# EasyEDA_Source_v2_e.net
KiCad netlist of a schematic drawn in EasyEDA
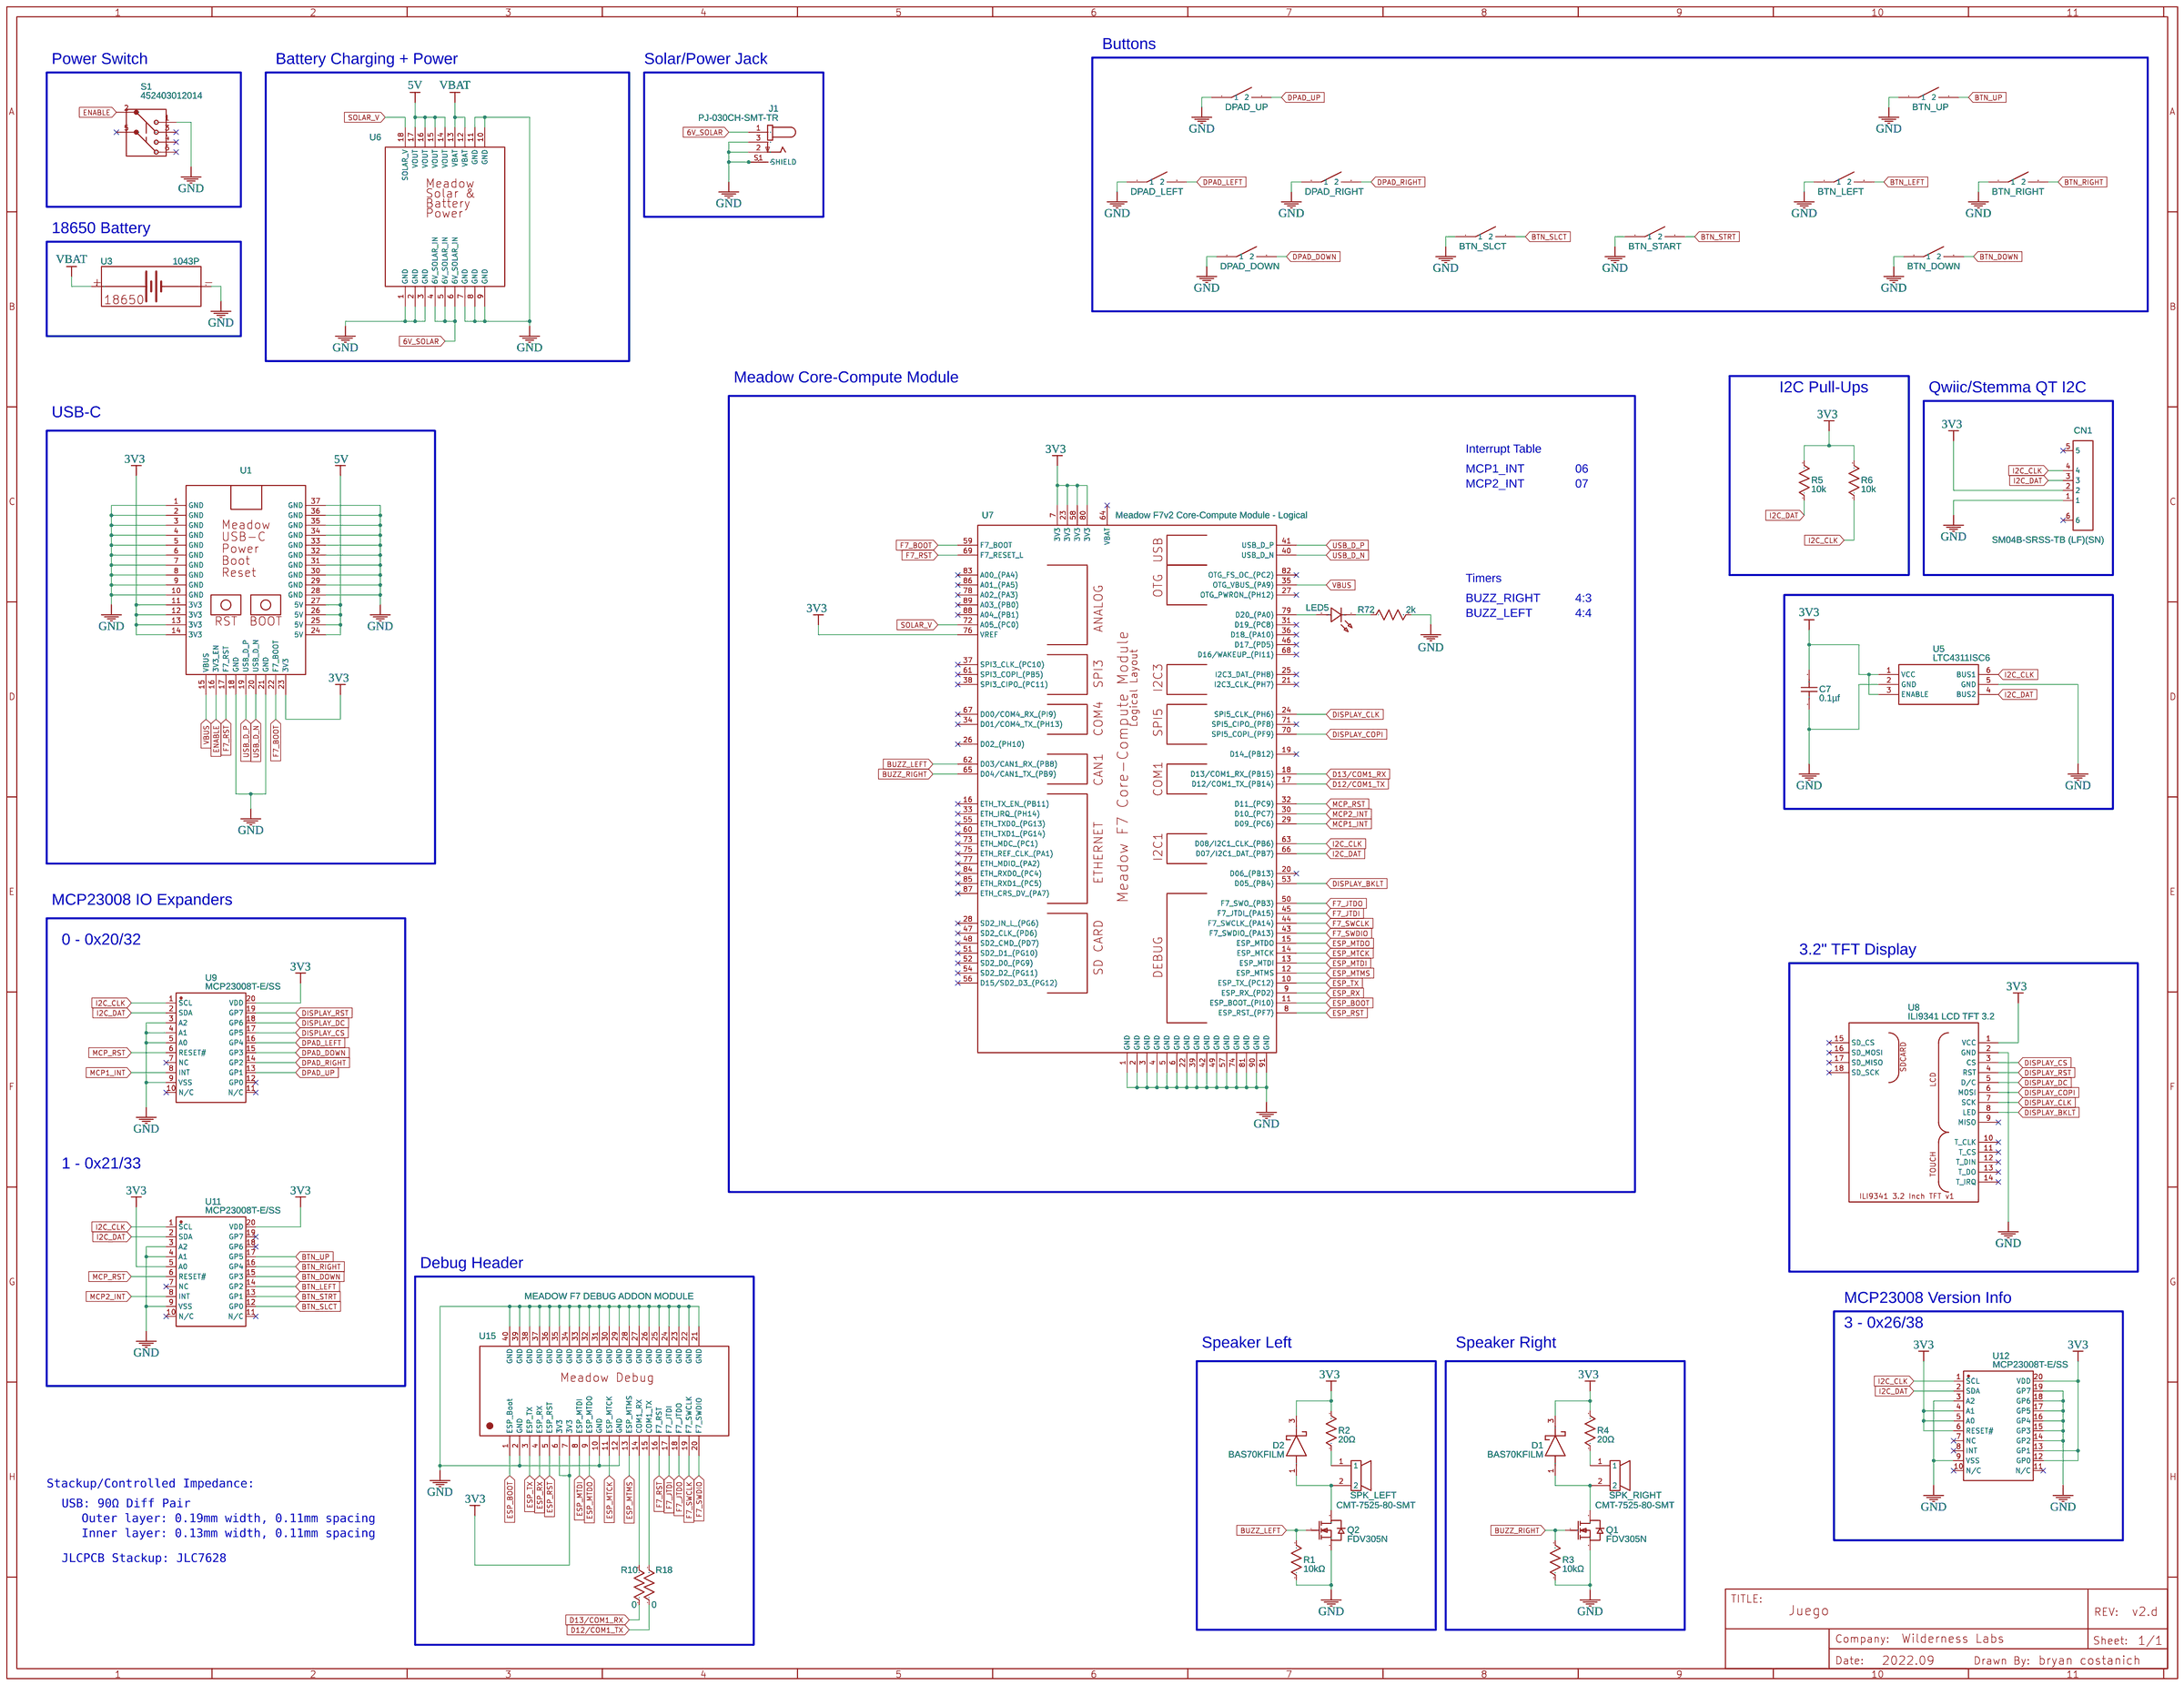
[diagram p0: schematic sheet]

(export (version "E")
  (design (tool "Eeschema 10.0.6"))
  (components
    (comp (ref "BTN_DOWN") (value "Up") (libsource (lib "") (part "Tactile Switch 6x6 SMD_5")))
    (comp (ref "BTN_LEFT") (value "Up") (libsource (lib "") (part "Tactile Switch 6x6 SMD_1")))
    (comp (ref "BTN_RIGHT") (value "Up") (libsource (lib "") (part "Tactile Switch 6x6 SMD_2")))
    (comp (ref "BTN_SLCT") (value "Up") (libsource (lib "") (part "Tactile Switch 6x6 SMD_6")))
    (comp (ref "BTN_START") (value "Up") (libsource (lib "") (part "Tactile Switch 6x6 SMD_8")))
    (comp (ref "BTN_UP") (value "Up") (libsource (lib "") (part "Tactile Switch 6x6 SMD_3")))
    (comp (ref "C7")
      (value "0.1µf")
      (fields
        (field (name "BOM_Manufacturer Part") "CC0603KRX7R7BB104")
        (field (name "BOM_Supplier Part") "C108079")
      )
      (libsource (lib "") (part "CC0603KRX7R7BB104"))
    )
    (comp (ref "CN1")
      (value "SM04B-SRSS-TB (LF)(SN)")
      (fields (field (name "BOM_Supplier Part") "C160404"))
      (libsource (lib "") (part "SM04B-SRSS-TB (LF)(SN)"))
    )
    (comp (ref "D1") (value "BAS70KFILM") (libsource (lib "") (part "BAS70KFILM")))
    (comp (ref "D2") (value "BAS70KFILM") (libsource (lib "") (part "BAS70KFILM")))
    (comp (ref "DPAD_DOWN") (value "Up") (libsource (lib "") (part "Tactile Switch 6x6 SMD")))
    (comp (ref "DPAD_LEFT") (value "Up") (libsource (lib "") (part "Tactile Switch 6x6 SMD_9")))
    (comp (ref "DPAD_RIGHT") (value "Up") (libsource (lib "") (part "Tactile Switch 6x6 SMD_7")))
    (comp (ref "DPAD_UP") (value "Up") (libsource (lib "") (part "Tactile Switch 6x6 SMD_4")))
    (comp (ref "J1") (value "PJ-030CH-SMT-TR") (libsource (lib "") (part "PJ-030CH-SMT-TR")))
    (comp (ref "LED5") (value "EAST1608GA0") (libsource (lib "") (part "EAST1608GA0")))
    (comp (ref "Q1")
      (value "FDV305N")
      (fields (field (name "BOM_Supplier Part") "C65189"))
      (libsource (lib "") (part "2N7002"))
    )
    (comp (ref "Q2")
      (value "FDV305N")
      (fields (field (name "BOM_Supplier Part") "C65189"))
      (libsource (lib "") (part "2N7002"))
    )
    (comp (ref "R1")
      (value "10kΩ")
      (fields (field (name "BOM_Manufacturer Part") "RC0603FR-0710KL"))
      (libsource (lib "") (part "R_0402_US"))
    )
    (comp (ref "R2")
      (value "20Ω")
      (fields (field (name "BOM_Manufacturer Part") "RC0603FR-0720RL"))
      (libsource (lib "") (part "R_0402_US"))
    )
    (comp (ref "R3")
      (value "10kΩ")
      (fields (field (name "BOM_Manufacturer Part") "RC0603FR-0710KL"))
      (libsource (lib "") (part "R_0402_US"))
    )
    (comp (ref "R4")
      (value "20Ω")
      (fields (field (name "BOM_Manufacturer Part") "RC0603FR-0720RL"))
      (libsource (lib "") (part "R_0402_US"))
    )
    (comp (ref "R5")
      (value "10k")
      (fields (field (name "BOM_Manufacturer Part") "RC0603FR-0710KL"))
      (libsource (lib "") (part "Res_0603(1/10W)_US"))
    )
    (comp (ref "R6")
      (value "10k")
      (fields (field (name "BOM_Manufacturer Part") "RC0603FR-0710KL"))
      (libsource (lib "") (part "Res_0603(1/10W)_US"))
    )
    (comp (ref "R10")
      (value "0")
      (fields (field (name "BOM_Manufacturer Part") "RC0603JR-070RL"))
      (libsource (lib "") (part "R_0603_US"))
    )
    (comp (ref "R18")
      (value "0")
      (fields (field (name "BOM_Manufacturer Part") "RC0603JR-070RL"))
      (libsource (lib "") (part "R_0603_US"))
    )
    (comp (ref "R72")
      (value "2k")
      (fields (field (name "BOM_Manufacturer Part") "RC0603FR-072KL"))
      (libsource (lib "") (part "R_0603_US_1"))
    )
    (comp (ref "S1") (value "452403012014") (libsource (lib "") (part "452403012014")))
    (comp (ref "SPK_LEFT")
      (value "CMT-7525-80-SMT")
      (fields (field (name "BOM_Manufacturer Part") "CMT-7525-80-SMT-TR"))
      (libsource (lib "") (part "CMT-7525-80-SMT"))
    )
    (comp (ref "SPK_RIGHT")
      (value "CMT-7525-80-SMT")
      (fields (field (name "BOM_Manufacturer Part") "CMT-7525-80-SMT-TR"))
      (libsource (lib "") (part "CMT-7525-80-SMT_1"))
    )
    (comp (ref "U1")
      (value "Meadow Core-Compute USB-C, Power, Boot, and Reset Addon Module")
      (libsource (lib "") (part "Meadow Core-Compute USB-C, Power, Boot, and Reset Addon Module"))
    )
    (comp (ref "U3") (value "1043P") (libsource (lib "") (part "1043P")))
    (comp (ref "U5")
      (value "LTC4311ISC6")
      (fields (field (name "BOM_Manufacturer Part") "LTC4311ISC6#TRPBF"))
      (libsource (lib "") (part "LTC4311ISC6"))
    )
    (comp (ref "U6")
      (value "Meadow Core-Compute Addon Module - Solar Battery Power")
      (libsource (lib "") (part "Meadow Core-Compute Addon Module - Solar Battery Power"))
    )
    (comp (ref "U7")
      (value "Meadow F7v2 Core-Compute Module - Logical")
      (libsource (lib "") (part "Meadow F7v2 Core-Compute Module - Logical"))
    )
    (comp (ref "U8") (value "ILI9341 LCD TFT 3.2") (libsource (lib "") (part "ILI9341 LCD TFT 3.2")))
    (comp (ref "U9")
      (value "MCP23008T-E/SS")
      (fields (field (name "BOM_Supplier Part") "C629435"))
      (libsource (lib "") (part "MCP23008T-E/SS"))
    )
    (comp (ref "U11")
      (value "MCP23008T-E/SS")
      (fields (field (name "BOM_Supplier Part") "C629435"))
      (libsource (lib "") (part "MCP23008T-E/SS"))
    )
    (comp (ref "U12")
      (value "MCP23008T-E/SS")
      (fields (field (name "BOM_Supplier Part") "C629435"))
      (libsource (lib "") (part "MCP23008T-E/SS"))
    )
    (comp (ref "U15")
      (value "MEADOW F7 DEBUG ADDON MODULE")
      (libsource (lib "") (part "MEADOW F7 DEBUG ADDON MODULE"))
    )
  )
  (nets
    (net (code "1") (name "3V3") (class "Default")
      (node (ref "C7") (pin "2") (pinfunction "2_2") (pintype "unspecified"))
      (node (ref "CN1") (pin "2") (pinfunction "2_2") (pintype "unspecified"))
      (node (ref "D1") (pin "3") (pinfunction "K_3") (pintype "bidirectional"))
      (node (ref "D2") (pin "3") (pinfunction "K_3") (pintype "bidirectional"))
      (node (ref "R2") (pin "2") (pinfunction "2_2") (pintype "unspecified"))
      (node (ref "R4") (pin "2") (pinfunction "2_2") (pintype "unspecified"))
      (node (ref "R5") (pin "2") (pinfunction "2_2") (pintype "unspecified"))
      (node (ref "R6") (pin "2") (pinfunction "2_2") (pintype "unspecified"))
      (node (ref "U1") (pin "11") (pinfunction "3V3_11") (pintype "unspecified"))
      (node (ref "U1") (pin "12") (pinfunction "3V3_12") (pintype "unspecified"))
      (node (ref "U1") (pin "13") (pinfunction "3V3_13") (pintype "unspecified"))
      (node (ref "U1") (pin "14") (pinfunction "3V3_14") (pintype "unspecified"))
      (node (ref "U1") (pin "23") (pinfunction "3V3_23") (pintype "passive"))
      (node (ref "U11") (pin "20") (pinfunction "VDD_20") (pintype "unspecified"))
      (node (ref "U11") (pin "5") (pinfunction "A0_5") (pintype "unspecified"))
      (node (ref "U12") (pin "12") (pinfunction "GP0_12") (pintype "unspecified"))
      (node (ref "U12") (pin "13") (pinfunction "GP1_13") (pintype "unspecified"))
      (node (ref "U12") (pin "20") (pinfunction "VDD_20") (pintype "unspecified"))
      (node (ref "U12") (pin "4") (pinfunction "A1_4") (pintype "unspecified"))
      (node (ref "U12") (pin "5") (pinfunction "A0_5") (pintype "unspecified"))
      (node (ref "U12") (pin "6") (pinfunction "RESET#_6") (pintype "unspecified"))
      (node (ref "U15") (pin "6") (pinfunction "3V3_6") (pintype "unspecified"))
      (node (ref "U15") (pin "7") (pinfunction "3V3_7") (pintype "unspecified"))
      (node (ref "U5") (pin "1") (pinfunction "VCC_1") (pintype "unspecified"))
      (node (ref "U5") (pin "3") (pinfunction "ENABLE_3") (pintype "unspecified"))
      (node (ref "U7") (pin "23") (pinfunction "3V3_23") (pintype "unspecified"))
      (node (ref "U7") (pin "58") (pinfunction "3V3_58") (pintype "passive"))
      (node (ref "U7") (pin "7") (pinfunction "3V3_7") (pintype "unspecified"))
      (node (ref "U7") (pin "76") (pinfunction "VREF_76") (pintype "input"))
      (node (ref "U7") (pin "80") (pinfunction "3V3_80") (pintype "unspecified"))
      (node (ref "U8") (pin "1") (pinfunction "VCC_1") (pintype "unspecified"))
      (node (ref "U9") (pin "20") (pinfunction "VDD_20") (pintype "unspecified"))
    )
    (net (code "2") (name "5V") (class "Default")
      (node (ref "U1") (pin "24") (pinfunction "5V_24") (pintype "passive"))
      (node (ref "U1") (pin "25") (pinfunction "5V_25") (pintype "passive"))
      (node (ref "U1") (pin "26") (pinfunction "5V_26") (pintype "passive"))
      (node (ref "U1") (pin "27") (pinfunction "5V_27") (pintype "passive"))
      (node (ref "U6") (pin "14") (pinfunction "VOUT_14") (pintype "unspecified"))
      (node (ref "U6") (pin "15") (pinfunction "VOUT_15") (pintype "unspecified"))
      (node (ref "U6") (pin "16") (pinfunction "VOUT_16") (pintype "unspecified"))
      (node (ref "U6") (pin "17") (pinfunction "VOUT_17") (pintype "unspecified"))
    )
    (net (code "3") (name "6V_SOLAR") (class "Default")
      (node (ref "J1") (pin "1") (pinfunction "1_1") (pintype "bidirectional"))
      (node (ref "U6") (pin "4") (pinfunction "6V_SOLAR_IN_4") (pintype "unspecified"))
      (node (ref "U6") (pin "5") (pinfunction "6V_SOLAR_IN_5") (pintype "unspecified"))
      (node (ref "U6") (pin "6") (pinfunction "6V_SOLAR_IN_6") (pintype "unspecified"))
    )
    (net (code "4") (name "BTN_DOWN") (class "Default")
      (node (ref "BTN_DOWN") (pin "B1") (pinfunction "2_B1") (pintype "unspecified"))
      (node (ref "U11") (pin "15") (pinfunction "GP3_15") (pintype "unspecified"))
    )
    (net (code "5") (name "BTN_LEFT") (class "Default")
      (node (ref "BTN_LEFT") (pin "B1") (pinfunction "2_B1") (pintype "unspecified"))
      (node (ref "U11") (pin "14") (pinfunction "GP2_14") (pintype "unspecified"))
    )
    (net (code "6") (name "BTN_RIGHT") (class "Default")
      (node (ref "BTN_RIGHT") (pin "B1") (pinfunction "2_B1") (pintype "unspecified"))
      (node (ref "U11") (pin "16") (pinfunction "GP4_16") (pintype "unspecified"))
    )
    (net (code "7") (name "BTN_SLCT") (class "Default")
      (node (ref "BTN_SLCT") (pin "B1") (pinfunction "2_B1") (pintype "unspecified"))
      (node (ref "U11") (pin "12") (pinfunction "GP0_12") (pintype "unspecified"))
    )
    (net (code "8") (name "BTN_STRT") (class "Default")
      (node (ref "BTN_START") (pin "B1") (pinfunction "2_B1") (pintype "unspecified"))
      (node (ref "U11") (pin "13") (pinfunction "GP1_13") (pintype "unspecified"))
    )
    (net (code "9") (name "BTN_UP") (class "Default")
      (node (ref "BTN_UP") (pin "B1") (pinfunction "2_B1") (pintype "unspecified"))
      (node (ref "U11") (pin "17") (pinfunction "GP5_17") (pintype "unspecified"))
    )
    (net (code "10") (name "BUZZ_LEFT") (class "Default")
      (node (ref "Q2") (pin "1") (pinfunction "G_1") (pintype "unspecified"))
      (node (ref "R1") (pin "2") (pinfunction "2_2") (pintype "unspecified"))
      (node (ref "U7") (pin "62") (pinfunction "D03/CAN1_RX_(PB8)_62") (pintype "unspecified"))
    )
    (net (code "11") (name "BUZZ_RIGHT") (class "Default")
      (node (ref "Q1") (pin "1") (pinfunction "G_1") (pintype "unspecified"))
      (node (ref "R3") (pin "2") (pinfunction "2_2") (pintype "unspecified"))
      (node (ref "U7") (pin "65") (pinfunction "D04/CAN1_TX_(PB9)_65") (pintype "unspecified"))
    )
    (net (code "12") (name "D12{slash}COM1_TX") (class "Default")
      (node (ref "R18") (pin "1") (pinfunction "1_1") (pintype "unspecified"))
      (node (ref "U7") (pin "17") (pinfunction "D12/COM1_TX_(PB14)_17") (pintype "unspecified"))
    )
    (net (code "13") (name "D13{slash}COM1_RX") (class "Default")
      (node (ref "R10") (pin "1") (pinfunction "1_1") (pintype "unspecified"))
      (node (ref "U7") (pin "18") (pinfunction "D13/COM1_RX_(PB15)_18") (pintype "unspecified"))
    )
    (net (code "14") (name "DISPLAY_BKLT") (class "Default")
      (node (ref "U7") (pin "53") (pinfunction "D05_(PB4)_53") (pintype "unspecified"))
      (node (ref "U8") (pin "8") (pinfunction "LED_8") (pintype "unspecified"))
    )
    (net (code "15") (name "DISPLAY_CLK") (class "Default")
      (node (ref "U7") (pin "24") (pinfunction "SPI5_CLK_(PH6)_24") (pintype "unspecified"))
      (node (ref "U8") (pin "7") (pinfunction "SCK_7") (pintype "unspecified"))
    )
    (net (code "16") (name "DISPLAY_COPI") (class "Default")
      (node (ref "U7") (pin "70") (pinfunction "SPI5_COPI_(PF9)_70") (pintype "unspecified"))
      (node (ref "U8") (pin "6") (pinfunction "MOSI_6") (pintype "unspecified"))
    )
    (net (code "17") (name "DISPLAY_CS") (class "Default")
      (node (ref "U8") (pin "3") (pinfunction "CS_3") (pintype "unspecified"))
      (node (ref "U9") (pin "17") (pinfunction "GP5_17") (pintype "unspecified"))
    )
    (net (code "18") (name "DISPLAY_DC") (class "Default")
      (node (ref "U8") (pin "5") (pinfunction "D/C_5") (pintype "unspecified"))
      (node (ref "U9") (pin "18") (pinfunction "GP6_18") (pintype "unspecified"))
    )
    (net (code "19") (name "DISPLAY_RST") (class "Default")
      (node (ref "U8") (pin "4") (pinfunction "RST_4") (pintype "unspecified"))
      (node (ref "U9") (pin "19") (pinfunction "GP7_19") (pintype "unspecified"))
    )
    (net (code "20") (name "DPAD_DOWN") (class "Default")
      (node (ref "DPAD_DOWN") (pin "B1") (pinfunction "2_B1") (pintype "unspecified"))
      (node (ref "U9") (pin "15") (pinfunction "GP3_15") (pintype "unspecified"))
    )
    (net (code "21") (name "DPAD_LEFT") (class "Default")
      (node (ref "DPAD_LEFT") (pin "B1") (pinfunction "2_B1") (pintype "unspecified"))
      (node (ref "U9") (pin "16") (pinfunction "GP4_16") (pintype "unspecified"))
    )
    (net (code "22") (name "DPAD_RIGHT") (class "Default")
      (node (ref "DPAD_RIGHT") (pin "B1") (pinfunction "2_B1") (pintype "unspecified"))
      (node (ref "U9") (pin "14") (pinfunction "GP2_14") (pintype "unspecified"))
    )
    (net (code "23") (name "DPAD_UP") (class "Default")
      (node (ref "DPAD_UP") (pin "B1") (pinfunction "2_B1") (pintype "unspecified"))
      (node (ref "U9") (pin "13") (pinfunction "GP1_13") (pintype "unspecified"))
    )
    (net (code "24") (name "ENABLE") (class "Default")
      (node (ref "S1") (pin "2") (pinfunction "1_2") (pintype "unspecified"))
      (node (ref "U1") (pin "16") (pinfunction "3V3_EN_16") (pintype "unspecified"))
    )
    (net (code "25") (name "ESP_BOOT") (class "Default")
      (node (ref "U15") (pin "1") (pinfunction "ESP_Boot_1") (pintype "unspecified"))
      (node (ref "U7") (pin "11") (pinfunction "ESP_BOOT_(PI10)_11") (pintype "unspecified"))
    )
    (net (code "26") (name "ESP_MTCK") (class "Default")
      (node (ref "U15") (pin "11") (pinfunction "ESP_MTCK_11") (pintype "unspecified"))
      (node (ref "U7") (pin "14") (pinfunction "ESP_MTCK_14") (pintype "unspecified"))
    )
    (net (code "27") (name "ESP_MTDI") (class "Default")
      (node (ref "U15") (pin "8") (pinfunction "ESP_MTDI_8") (pintype "unspecified"))
      (node (ref "U7") (pin "13") (pinfunction "ESP_MTDI_13") (pintype "unspecified"))
    )
    (net (code "28") (name "ESP_MTDO") (class "Default")
      (node (ref "U15") (pin "9") (pinfunction "ESP_MTDO_9") (pintype "unspecified"))
      (node (ref "U7") (pin "15") (pinfunction "ESP_MTDO_15") (pintype "unspecified"))
    )
    (net (code "29") (name "ESP_MTMS") (class "Default")
      (node (ref "U15") (pin "13") (pinfunction "ESP_MTMS_13") (pintype "unspecified"))
      (node (ref "U7") (pin "12") (pinfunction "ESP_MTMS_12") (pintype "unspecified"))
    )
    (net (code "30") (name "ESP_RST") (class "Default")
      (node (ref "U15") (pin "5") (pinfunction "ESP_RST_5") (pintype "unspecified"))
      (node (ref "U7") (pin "8") (pinfunction "ESP_RST_(PF7)_8") (pintype "unspecified"))
    )
    (net (code "31") (name "ESP_RX") (class "Default")
      (node (ref "U15") (pin "4") (pinfunction "ESP_RX_4") (pintype "unspecified"))
      (node (ref "U7") (pin "9") (pinfunction "ESP_RX_(PD2)_9") (pintype "unspecified"))
    )
    (net (code "32") (name "ESP_TX") (class "Default")
      (node (ref "U15") (pin "3") (pinfunction "ESP_TX_3") (pintype "unspecified"))
      (node (ref "U7") (pin "10") (pinfunction "ESP_TX_(PC12)_10") (pintype "unspecified"))
    )
    (net (code "33") (name "F7_BOOT") (class "Default")
      (node (ref "U1") (pin "22") (pinfunction "F7_BOOT_22") (pintype "unspecified"))
      (node (ref "U7") (pin "59") (pinfunction "F7_BOOT_59") (pintype "unspecified"))
    )
    (net (code "34") (name "F7_JTDI") (class "Default")
      (node (ref "U15") (pin "17") (pinfunction "F7_JTDI_17") (pintype "unspecified"))
      (node (ref "U7") (pin "45") (pinfunction "F7_JTDI_(PA15)_45") (pintype "unspecified"))
    )
    (net (code "35") (name "F7_JTDO") (class "Default")
      (node (ref "U15") (pin "18") (pinfunction "F7_JTDO_18") (pintype "unspecified"))
      (node (ref "U7") (pin "50") (pinfunction "F7_SWO_(PB3)_50") (pintype "unspecified"))
    )
    (net (code "36") (name "F7_RST") (class "Default")
      (node (ref "U1") (pin "17") (pinfunction "F7_RST_17") (pintype "unspecified"))
      (node (ref "U15") (pin "16") (pinfunction "F7_RST_16") (pintype "unspecified"))
      (node (ref "U7") (pin "69") (pinfunction "F7_RESET_L_69") (pintype "unspecified"))
    )
    (net (code "37") (name "F7_SWCLK") (class "Default")
      (node (ref "U15") (pin "19") (pinfunction "F7_SWCLK_19") (pintype "unspecified"))
      (node (ref "U7") (pin "44") (pinfunction "F7_SWCLK_(PA14)_44") (pintype "unspecified"))
    )
    (net (code "38") (name "F7_SWDIO") (class "Default")
      (node (ref "U15") (pin "20") (pinfunction "F7_SWDIO_20") (pintype "unspecified"))
      (node (ref "U7") (pin "43") (pinfunction "F7_SWDIO_(PA13)_43") (pintype "unspecified"))
    )
    (net (code "39") (name "GND") (class "Default")
      (node (ref "BTN_DOWN") (pin "A1") (pinfunction "1_A1") (pintype "unspecified"))
      (node (ref "BTN_LEFT") (pin "A1") (pinfunction "1_A1") (pintype "unspecified"))
      (node (ref "BTN_RIGHT") (pin "A1") (pinfunction "1_A1") (pintype "unspecified"))
      (node (ref "BTN_SLCT") (pin "A1") (pinfunction "1_A1") (pintype "unspecified"))
      (node (ref "BTN_START") (pin "A1") (pinfunction "1_A1") (pintype "unspecified"))
      (node (ref "BTN_UP") (pin "A1") (pinfunction "1_A1") (pintype "unspecified"))
      (node (ref "C7") (pin "1") (pinfunction "1_1") (pintype "unspecified"))
      (node (ref "CN1") (pin "1") (pinfunction "1_1") (pintype "unspecified"))
      (node (ref "DPAD_DOWN") (pin "A1") (pinfunction "1_A1") (pintype "unspecified"))
      (node (ref "DPAD_LEFT") (pin "A1") (pinfunction "1_A1") (pintype "unspecified"))
      (node (ref "DPAD_RIGHT") (pin "A1") (pinfunction "1_A1") (pintype "unspecified"))
      (node (ref "DPAD_UP") (pin "A1") (pinfunction "1_A1") (pintype "unspecified"))
      (node (ref "J1") (pin "2") (pinfunction "2_2") (pintype "bidirectional"))
      (node (ref "J1") (pin "3") (pinfunction "3_3") (pintype "bidirectional"))
      (node (ref "J1") (pin "S1") (pinfunction "SHIELD_S1") (pintype "bidirectional"))
      (node (ref "J1") (pin "S2") (pinfunction "SHIELD_S2") (pintype "bidirectional"))
      (node (ref "Q1") (pin "2") (pinfunction "S_2") (pintype "unspecified"))
      (node (ref "Q2") (pin "2") (pinfunction "S_2") (pintype "unspecified"))
      (node (ref "R1") (pin "1") (pinfunction "1_1") (pintype "unspecified"))
      (node (ref "R3") (pin "1") (pinfunction "1_1") (pintype "unspecified"))
      (node (ref "R72") (pin "2") (pinfunction "2_2") (pintype "unspecified"))
      (node (ref "S1") (pin "1") (pinfunction "1_1") (pintype "unspecified"))
      (node (ref "U1") (pin "1") (pinfunction "GND_1") (pintype "unspecified"))
      (node (ref "U1") (pin "10") (pinfunction "GND_10") (pintype "unspecified"))
      (node (ref "U1") (pin "18") (pinfunction "GND_18") (pintype "unspecified"))
      (node (ref "U1") (pin "2") (pinfunction "GND_2") (pintype "unspecified"))
      (node (ref "U1") (pin "21") (pinfunction "GND_21") (pintype "unspecified"))
      (node (ref "U1") (pin "28") (pinfunction "GND_28") (pintype "unspecified"))
      (node (ref "U1") (pin "29") (pinfunction "GND_29") (pintype "unspecified"))
      (node (ref "U1") (pin "3") (pinfunction "GND_3") (pintype "unspecified"))
      (node (ref "U1") (pin "30") (pinfunction "GND_30") (pintype "unspecified"))
      (node (ref "U1") (pin "31") (pinfunction "GND_31") (pintype "unspecified"))
      (node (ref "U1") (pin "32") (pinfunction "GND_32") (pintype "unspecified"))
      (node (ref "U1") (pin "33") (pinfunction "GND_33") (pintype "unspecified"))
      (node (ref "U1") (pin "34") (pinfunction "GND_34") (pintype "unspecified"))
      (node (ref "U1") (pin "35") (pinfunction "GND_35") (pintype "unspecified"))
      (node (ref "U1") (pin "36") (pinfunction "GND_36") (pintype "unspecified"))
      (node (ref "U1") (pin "37") (pinfunction "GND_37") (pintype "unspecified"))
      (node (ref "U1") (pin "4") (pinfunction "GND_4") (pintype "unspecified"))
      (node (ref "U1") (pin "5") (pinfunction "GND_5") (pintype "unspecified"))
      (node (ref "U1") (pin "6") (pinfunction "GND_6") (pintype "unspecified"))
      (node (ref "U1") (pin "7") (pinfunction "GND_7") (pintype "unspecified"))
      (node (ref "U1") (pin "8") (pinfunction "GND_8") (pintype "unspecified"))
      (node (ref "U1") (pin "9") (pinfunction "GND_9") (pintype "unspecified"))
      (node (ref "U11") (pin "3") (pinfunction "A2_3") (pintype "unspecified"))
      (node (ref "U11") (pin "4") (pinfunction "A1_4") (pintype "unspecified"))
      (node (ref "U11") (pin "9") (pinfunction "VSS_9") (pintype "unspecified"))
      (node (ref "U12") (pin "14") (pinfunction "GP2_14") (pintype "unspecified"))
      (node (ref "U12") (pin "15") (pinfunction "GP3_15") (pintype "unspecified"))
      (node (ref "U12") (pin "16") (pinfunction "GP4_16") (pintype "unspecified"))
      (node (ref "U12") (pin "17") (pinfunction "GP5_17") (pintype "unspecified"))
      (node (ref "U12") (pin "18") (pinfunction "GP6_18") (pintype "unspecified"))
      (node (ref "U12") (pin "19") (pinfunction "GP7_19") (pintype "unspecified"))
      (node (ref "U12") (pin "3") (pinfunction "A2_3") (pintype "unspecified"))
      (node (ref "U12") (pin "9") (pinfunction "VSS_9") (pintype "unspecified"))
      (node (ref "U15") (pin "10") (pinfunction "GND_10") (pintype "unspecified"))
      (node (ref "U15") (pin "12") (pinfunction "GND_12") (pintype "unspecified"))
      (node (ref "U15") (pin "2") (pinfunction "GND_2") (pintype "unspecified"))
      (node (ref "U15") (pin "21") (pinfunction "GND_21") (pintype "unspecified"))
      (node (ref "U15") (pin "22") (pinfunction "GND_22") (pintype "unspecified"))
      (node (ref "U15") (pin "23") (pinfunction "GND_23") (pintype "unspecified"))
      (node (ref "U15") (pin "24") (pinfunction "GND_24") (pintype "unspecified"))
      (node (ref "U15") (pin "25") (pinfunction "GND_25") (pintype "unspecified"))
      (node (ref "U15") (pin "26") (pinfunction "GND_26") (pintype "unspecified"))
      (node (ref "U15") (pin "27") (pinfunction "GND_27") (pintype "unspecified"))
      (node (ref "U15") (pin "28") (pinfunction "GND_28") (pintype "unspecified"))
      (node (ref "U15") (pin "29") (pinfunction "GND_29") (pintype "unspecified"))
      (node (ref "U15") (pin "30") (pinfunction "GND_30") (pintype "unspecified"))
      (node (ref "U15") (pin "31") (pinfunction "GND_31") (pintype "unspecified"))
      (node (ref "U15") (pin "32") (pinfunction "GND_32") (pintype "unspecified"))
      (node (ref "U15") (pin "33") (pinfunction "GND_33") (pintype "unspecified"))
      (node (ref "U15") (pin "34") (pinfunction "GND_34") (pintype "unspecified"))
      (node (ref "U15") (pin "35") (pinfunction "GND_35") (pintype "unspecified"))
      (node (ref "U15") (pin "36") (pinfunction "GND_36") (pintype "unspecified"))
      (node (ref "U15") (pin "37") (pinfunction "GND_37") (pintype "unspecified"))
      (node (ref "U15") (pin "38") (pinfunction "GND_38") (pintype "unspecified"))
      (node (ref "U15") (pin "39") (pinfunction "GND_39") (pintype "unspecified"))
      (node (ref "U15") (pin "40") (pinfunction "GND_40") (pintype "unspecified"))
      (node (ref "U3") (pin "2") (pinfunction "-_2") (pintype "passive"))
      (node (ref "U5") (pin "2") (pinfunction "GND_2") (pintype "unspecified"))
      (node (ref "U5") (pin "5") (pinfunction "GND_5") (pintype "unspecified"))
      (node (ref "U6") (pin "1") (pinfunction "GND_1") (pintype "unspecified"))
      (node (ref "U6") (pin "10") (pinfunction "GND_10") (pintype "unspecified"))
      (node (ref "U6") (pin "11") (pinfunction "GND_11") (pintype "unspecified"))
      (node (ref "U6") (pin "2") (pinfunction "GND_2") (pintype "unspecified"))
      (node (ref "U6") (pin "3") (pinfunction "GND_3") (pintype "unspecified"))
      (node (ref "U6") (pin "7") (pinfunction "GND_7") (pintype "unspecified"))
      (node (ref "U6") (pin "8") (pinfunction "GND_8") (pintype "unspecified"))
      (node (ref "U6") (pin "9") (pinfunction "GND_9") (pintype "unspecified"))
      (node (ref "U7") (pin "1") (pinfunction "GND_1") (pintype "passive"))
      (node (ref "U7") (pin "2") (pinfunction "GND_2") (pintype "passive"))
      (node (ref "U7") (pin "22") (pinfunction "GND_22") (pintype "passive"))
      (node (ref "U7") (pin "3") (pinfunction "GND_3") (pintype "passive"))
      (node (ref "U7") (pin "39") (pinfunction "GND_39") (pintype "passive"))
      (node (ref "U7") (pin "4") (pinfunction "GND_4") (pintype "passive"))
      (node (ref "U7") (pin "42") (pinfunction "GND_42") (pintype "passive"))
      (node (ref "U7") (pin "49") (pinfunction "GND_49") (pintype "passive"))
      (node (ref "U7") (pin "5") (pinfunction "GND_5") (pintype "passive"))
      (node (ref "U7") (pin "57") (pinfunction "GND_57") (pintype "passive"))
      (node (ref "U7") (pin "6") (pinfunction "GND_6") (pintype "passive"))
      (node (ref "U7") (pin "74") (pinfunction "GND_74") (pintype "passive"))
      (node (ref "U7") (pin "81") (pinfunction "GND_81") (pintype "passive"))
      (node (ref "U7") (pin "90") (pinfunction "GND_90") (pintype "passive"))
      (node (ref "U7") (pin "91") (pinfunction "GND_91") (pintype "passive"))
      (node (ref "U8") (pin "2") (pinfunction "GND_2") (pintype "unspecified"))
      (node (ref "U9") (pin "3") (pinfunction "A2_3") (pintype "unspecified"))
      (node (ref "U9") (pin "4") (pinfunction "A1_4") (pintype "unspecified"))
      (node (ref "U9") (pin "5") (pinfunction "A0_5") (pintype "unspecified"))
      (node (ref "U9") (pin "9") (pinfunction "VSS_9") (pintype "unspecified"))
    )
    (net (code "40") (name "I2C_CLK") (class "Default")
      (node (ref "CN1") (pin "4") (pinfunction "4_4") (pintype "unspecified"))
      (node (ref "R6") (pin "1") (pinfunction "1_1") (pintype "unspecified"))
      (node (ref "U11") (pin "1") (pinfunction "SCL_1") (pintype "unspecified"))
      (node (ref "U12") (pin "1") (pinfunction "SCL_1") (pintype "unspecified"))
      (node (ref "U5") (pin "6") (pinfunction "BUS1_6") (pintype "unspecified"))
      (node (ref "U7") (pin "63") (pinfunction "D08/I2C1_CLK_(PB6)_63") (pintype "unspecified"))
      (node (ref "U9") (pin "1") (pinfunction "SCL_1") (pintype "unspecified"))
    )
    (net (code "41") (name "I2C_DAT") (class "Default")
      (node (ref "CN1") (pin "3") (pinfunction "3_3") (pintype "unspecified"))
      (node (ref "R5") (pin "1") (pinfunction "1_1") (pintype "unspecified"))
      (node (ref "U11") (pin "2") (pinfunction "SDA_2") (pintype "unspecified"))
      (node (ref "U12") (pin "2") (pinfunction "SDA_2") (pintype "unspecified"))
      (node (ref "U5") (pin "4") (pinfunction "BUS2_4") (pintype "unspecified"))
      (node (ref "U7") (pin "66") (pinfunction "D07/I2C1_DAT_(PB7)_66") (pintype "unspecified"))
      (node (ref "U9") (pin "2") (pinfunction "SDA_2") (pintype "unspecified"))
    )
    (net (code "42") (name "MCP1_INT") (class "Default")
      (node (ref "U7") (pin "29") (pinfunction "D09_(PC6)_29") (pintype "unspecified"))
      (node (ref "U9") (pin "8") (pinfunction "INT_8") (pintype "unspecified"))
    )
    (net (code "43") (name "MCP2_INT") (class "Default")
      (node (ref "U11") (pin "8") (pinfunction "INT_8") (pintype "unspecified"))
      (node (ref "U7") (pin "30") (pinfunction "D10_(PC7)_30") (pintype "unspecified"))
    )
    (net (code "44") (name "MCP_RST") (class "Default")
      (node (ref "U11") (pin "6") (pinfunction "RESET#_6") (pintype "unspecified"))
      (node (ref "U7") (pin "32") (pinfunction "D11_(PC9)_32") (pintype "unspecified"))
      (node (ref "U9") (pin "6") (pinfunction "RESET#_6") (pintype "unspecified"))
    )
    (net (code "45") (name "Net-(D1-A)") (class "Default")
      (node (ref "D1") (pin "1") (pinfunction "A_1") (pintype "bidirectional"))
      (node (ref "Q1") (pin "3") (pinfunction "D_3") (pintype "unspecified"))
      (node (ref "SPK_RIGHT") (pin "2") (pinfunction "2_2") (pintype "unspecified"))
    )
    (net (code "46") (name "Net-(D2-A)") (class "Default")
      (node (ref "D2") (pin "1") (pinfunction "A_1") (pintype "bidirectional"))
      (node (ref "Q2") (pin "3") (pinfunction "D_3") (pintype "unspecified"))
      (node (ref "SPK_LEFT") (pin "2") (pinfunction "2_2") (pintype "unspecified"))
    )
    (net (code "47") (name "Net-(LED5-A)") (class "Default")
      (node (ref "LED5") (pin "2") (pinfunction "A_2") (pintype "unspecified"))
      (node (ref "U7") (pin "79") (pinfunction "D20_(PA0)_79") (pintype "unspecified"))
    )
    (net (code "48") (name "Net-(LED5-K)") (class "Default")
      (node (ref "LED5") (pin "1") (pinfunction "K_1") (pintype "unspecified"))
      (node (ref "R72") (pin "1") (pinfunction "1_1") (pintype "unspecified"))
    )
    (net (code "49") (name "Net-(R2-Pad1)") (class "Default")
      (node (ref "R2") (pin "1") (pinfunction "1_1") (pintype "unspecified"))
      (node (ref "SPK_LEFT") (pin "1") (pinfunction "1_1") (pintype "unspecified"))
    )
    (net (code "50") (name "Net-(R4-Pad1)") (class "Default")
      (node (ref "R4") (pin "1") (pinfunction "1_1") (pintype "unspecified"))
      (node (ref "SPK_RIGHT") (pin "1") (pinfunction "1_1") (pintype "unspecified"))
    )
    (net (code "51") (name "Net-(U15-COM1_RX)") (class "Default")
      (node (ref "R10") (pin "2") (pinfunction "2_2") (pintype "unspecified"))
      (node (ref "U15") (pin "14") (pinfunction "COM1_RX_14") (pintype "unspecified"))
    )
    (net (code "52") (name "Net-(U15-COM1_TX)") (class "Default")
      (node (ref "R18") (pin "2") (pinfunction "2_2") (pintype "unspecified"))
      (node (ref "U15") (pin "15") (pinfunction "COM1_TX_15") (pintype "unspecified"))
    )
    (net (code "53") (name "SOLAR_V") (class "Default")
      (node (ref "U6") (pin "18") (pinfunction "SOLAR_V_18") (pintype "unspecified"))
      (node (ref "U7") (pin "72") (pinfunction "A05_(PC0)_72") (pintype "unspecified"))
    )
    (net (code "54") (name "USB_D_N") (class "Default")
      (node (ref "U1") (pin "20") (pinfunction "USB_D_N_20") (pintype "unspecified"))
      (node (ref "U7") (pin "40") (pinfunction "USB_D_N_40") (pintype "unspecified"))
    )
    (net (code "55") (name "USB_D_P") (class "Default")
      (node (ref "U1") (pin "19") (pinfunction "USB_D_P_19") (pintype "unspecified"))
      (node (ref "U7") (pin "41") (pinfunction "USB_D_P_41") (pintype "unspecified"))
    )
    (net (code "56") (name "VBAT") (class "Default")
      (node (ref "U3") (pin "1") (pinfunction "+_1") (pintype "passive"))
      (node (ref "U6") (pin "12") (pinfunction "VBAT_12") (pintype "unspecified"))
      (node (ref "U6") (pin "13") (pinfunction "VBAT_13") (pintype "unspecified"))
    )
    (net (code "57") (name "VBUS") (class "Default")
      (node (ref "U1") (pin "15") (pinfunction "VBUS_15") (pintype "unspecified"))
      (node (ref "U7") (pin "35") (pinfunction "OTG_VBUS_(PA9)_35") (pintype "unspecified"))
    )
    (net (code "58") (name "unconnected-(CN1-Pad5)") (class "Default")
      (node (ref "CN1") (pin "5") (pinfunction "5_5") (pintype "unspecified+no_connect"))
    )
    (net (code "59") (name "unconnected-(CN1-Pad6)") (class "Default")
      (node (ref "CN1") (pin "6") (pinfunction "6_6") (pintype "unspecified+no_connect"))
    )
    (net (code "60") (name "unconnected-(S1-1-Pad3)") (class "Default")
      (node (ref "S1") (pin "3") (pinfunction "1_3") (pintype "unspecified+no_connect"))
    )
    (net (code "61") (name "unconnected-(S1-1-Pad4)") (class "Default")
      (node (ref "S1") (pin "4") (pinfunction "1_4") (pintype "unspecified+no_connect"))
    )
    (net (code "62") (name "unconnected-(S1-1-Pad6)") (class "Default")
      (node (ref "S1") (pin "6") (pinfunction "1_6") (pintype "unspecified+no_connect"))
    )
    (net (code "63") (name "unconnected-(S1-2-Pad5)") (class "Default")
      (node (ref "S1") (pin "5") (pinfunction "2_5") (pintype "unspecified+no_connect"))
    )
    (net (code "64") (name "unconnected-(U7-A00_(PA4)-Pad83)") (class "Default")
      (node (ref "U7") (pin "83") (pinfunction "A00_(PA4)_83") (pintype "unspecified+no_connect"))
    )
    (net (code "65") (name "unconnected-(U7-A01_(PA5)-Pad86)") (class "Default")
      (node (ref "U7") (pin "86") (pinfunction "A01_(PA5)_86") (pintype "unspecified+no_connect"))
    )
    (net (code "66") (name "unconnected-(U7-A02_(PA3)-Pad78)") (class "Default")
      (node (ref "U7") (pin "78") (pinfunction "A02_(PA3)_78") (pintype "unspecified+no_connect"))
    )
    (net (code "67") (name "unconnected-(U7-A03_(PB0)-Pad89)") (class "Default")
      (node (ref "U7") (pin "89") (pinfunction "A03_(PB0)_89") (pintype "unspecified+no_connect"))
    )
    (net (code "68") (name "unconnected-(U7-A04_(PB1)-Pad88)") (class "Default")
      (node (ref "U7") (pin "88") (pinfunction "A04_(PB1)_88") (pintype "unspecified+no_connect"))
    )
    (net (code "69") (name "unconnected-(U7-D00{slash}COM4_RX_(PI9)-Pad67)") (class "Default")
      (node (ref "U7") (pin "67") (pinfunction "D00/COM4_RX_(PI9)_67") (pintype "unspecified+no_connect"))
    )
    (net (code "70") (name "unconnected-(U7-D01{slash}COM4_TX_(PH13)-Pad34)") (class "Default")
      (node (ref "U7") (pin "34") (pinfunction "D01/COM4_TX_(PH13)_34") (pintype "unspecified+no_connect"))
    )
    (net (code "71") (name "unconnected-(U7-D02_(PH10)-Pad26)") (class "Default")
      (node (ref "U7") (pin "26") (pinfunction "D02_(PH10)_26") (pintype "unspecified+no_connect"))
    )
    (net (code "72") (name "unconnected-(U7-D06_(PB13)-Pad20)") (class "Default")
      (node (ref "U7") (pin "20") (pinfunction "D06_(PB13)_20") (pintype "unspecified+no_connect"))
    )
    (net (code "73") (name "unconnected-(U7-D14_(PB12)-Pad19)") (class "Default")
      (node (ref "U7") (pin "19") (pinfunction "D14_(PB12)_19") (pintype "unspecified+no_connect"))
    )
    (net (code "74") (name "unconnected-(U7-D15{slash}SD2_D3_(PG12)-Pad56)") (class "Default")
      (node (ref "U7") (pin "56") (pinfunction "D15/SD2_D3_(PG12)_56") (pintype "unspecified+no_connect"))
    )
    (net (code "75") (name "unconnected-(U7-D16{slash}WAKEUP_(PI11)-Pad68)") (class "Default")
      (node (ref "U7") (pin "68") (pinfunction "D16/WAKEUP_(PI11)_68") (pintype "unspecified+no_connect"))
    )
    (net (code "76") (name "unconnected-(U7-D17_(PD5)-Pad46)") (class "Default")
      (node (ref "U7") (pin "46") (pinfunction "D17_(PD5)_46") (pintype "unspecified+no_connect"))
    )
    (net (code "77") (name "unconnected-(U7-D18_(PA10)-Pad36)") (class "Default")
      (node (ref "U7") (pin "36") (pinfunction "D18_(PA10)_36") (pintype "unspecified+no_connect"))
    )
    (net (code "78") (name "unconnected-(U7-D19_(PC8)-Pad31)") (class "Default")
      (node (ref "U7") (pin "31") (pinfunction "D19_(PC8)_31") (pintype "unspecified+no_connect"))
    )
    (net (code "79") (name "unconnected-(U7-ETH_CRS_DV_(PA7)-Pad87)") (class "Default")
      (node (ref "U7") (pin "87") (pinfunction "ETH_CRS_DV_(PA7)_87") (pintype "unspecified+no_connect"))
    )
    (net (code "80") (name "unconnected-(U7-ETH_IRQ_(PH14)-Pad33)") (class "Default")
      (node (ref "U7") (pin "33") (pinfunction "ETH_IRQ_(PH14)_33") (pintype "unspecified+no_connect"))
    )
    (net (code "81") (name "unconnected-(U7-ETH_MDC_(PC1)-Pad73)") (class "Default")
      (node (ref "U7") (pin "73") (pinfunction "ETH_MDC_(PC1)_73") (pintype "unspecified+no_connect"))
    )
    (net (code "82") (name "unconnected-(U7-ETH_MDIO_(PA2)-Pad77)") (class "Default")
      (node (ref "U7") (pin "77") (pinfunction "ETH_MDIO_(PA2)_77") (pintype "unspecified+no_connect"))
    )
    (net (code "83") (name "unconnected-(U7-ETH_REF_CLK_(PA1)-Pad75)") (class "Default")
      (node (ref "U7") (pin "75") (pinfunction "ETH_REF_CLK_(PA1)_75") (pintype "unspecified+no_connect"))
    )
    (net (code "84") (name "unconnected-(U7-ETH_RXD0_(PC4)-Pad84)") (class "Default")
      (node (ref "U7") (pin "84") (pinfunction "ETH_RXD0_(PC4)_84") (pintype "unspecified+no_connect"))
    )
    (net (code "85") (name "unconnected-(U7-ETH_RXD1_(PC5)-Pad85)") (class "Default")
      (node (ref "U7") (pin "85") (pinfunction "ETH_RXD1_(PC5)_85") (pintype "unspecified+no_connect"))
    )
    (net (code "86") (name "unconnected-(U7-ETH_TXD0_(PG13)-Pad55)") (class "Default")
      (node (ref "U7") (pin "55") (pinfunction "ETH_TXD0_(PG13)_55") (pintype "unspecified+no_connect"))
    )
    (net (code "87") (name "unconnected-(U7-ETH_TXD1_(PG14)-Pad60)") (class "Default")
      (node (ref "U7") (pin "60") (pinfunction "ETH_TXD1_(PG14)_60") (pintype "unspecified+no_connect"))
    )
    (net (code "88") (name "unconnected-(U7-ETH_TX_EN_(PB11)-Pad16)") (class "Default")
      (node (ref "U7") (pin "16") (pinfunction "ETH_TX_EN_(PB11)_16") (pintype "unspecified+no_connect"))
    )
    (net (code "89") (name "unconnected-(U7-I2C3_CLK_(PH7)-Pad21)") (class "Default")
      (node (ref "U7") (pin "21") (pinfunction "I2C3_CLK_(PH7)_21") (pintype "unspecified+no_connect"))
    )
    (net (code "90") (name "unconnected-(U7-I2C3_DAT_(PH8)-Pad25)") (class "Default")
      (node (ref "U7") (pin "25") (pinfunction "I2C3_DAT_(PH8)_25") (pintype "unspecified+no_connect"))
    )
    (net (code "91") (name "unconnected-(U7-OTG_FS_OC_(PC2)-Pad82)") (class "Default")
      (node (ref "U7") (pin "82") (pinfunction "OTG_FS_OC_(PC2)_82") (pintype "unspecified+no_connect"))
    )
    (net (code "92") (name "unconnected-(U7-OTG_PWRON_(PH12)-Pad27)") (class "Default")
      (node (ref "U7") (pin "27") (pinfunction "OTG_PWRON_(PH12)_27") (pintype "unspecified+no_connect"))
    )
    (net (code "93") (name "unconnected-(U7-SD2_CLK_(PD6)-Pad47)") (class "Default")
      (node (ref "U7") (pin "47") (pinfunction "SD2_CLK_(PD6)_47") (pintype "unspecified+no_connect"))
    )
    (net (code "94") (name "unconnected-(U7-SD2_CMD_(PD7)-Pad48)") (class "Default")
      (node (ref "U7") (pin "48") (pinfunction "SD2_CMD_(PD7)_48") (pintype "unspecified+no_connect"))
    )
    (net (code "95") (name "unconnected-(U7-SD2_D0_(PG9)-Pad52)") (class "Default")
      (node (ref "U7") (pin "52") (pinfunction "SD2_D0_(PG9)_52") (pintype "unspecified+no_connect"))
    )
    (net (code "96") (name "unconnected-(U7-SD2_D1_(PG10)-Pad51)") (class "Default")
      (node (ref "U7") (pin "51") (pinfunction "SD2_D1_(PG10)_51") (pintype "unspecified+no_connect"))
    )
    (net (code "97") (name "unconnected-(U7-SD2_D2_(PG11)-Pad54)") (class "Default")
      (node (ref "U7") (pin "54") (pinfunction "SD2_D2_(PG11)_54") (pintype "unspecified+no_connect"))
    )
    (net (code "98") (name "unconnected-(U7-SD2_IN_L_(PG6)-Pad28)") (class "Default")
      (node (ref "U7") (pin "28") (pinfunction "SD2_IN_L_(PG6)_28") (pintype "unspecified+no_connect"))
    )
    (net (code "99") (name "unconnected-(U7-SPI3_CIPO_(PC11)-Pad38)") (class "Default")
      (node (ref "U7") (pin "38") (pinfunction "SPI3_CIPO_(PC11)_38") (pintype "unspecified+no_connect"))
    )
    (net (code "100") (name "unconnected-(U7-SPI3_CLK_(PC10)-Pad37)") (class "Default")
      (node (ref "U7") (pin "37") (pinfunction "SPI3_CLK_(PC10)_37") (pintype "unspecified+no_connect"))
    )
    (net (code "101") (name "unconnected-(U7-SPI3_COPI_(PB5)-Pad61)") (class "Default")
      (node (ref "U7") (pin "61") (pinfunction "SPI3_COPI_(PB5)_61") (pintype "unspecified+no_connect"))
    )
    (net (code "102") (name "unconnected-(U7-SPI5_CIPO_(PF8)-Pad71)") (class "Default")
      (node (ref "U7") (pin "71") (pinfunction "SPI5_CIPO_(PF8)_71") (pintype "unspecified+no_connect"))
    )
    (net (code "103") (name "unconnected-(U7-VBAT-Pad64)") (class "Default")
      (node (ref "U7") (pin "64") (pinfunction "VBAT_64") (pintype "input+no_connect"))
    )
    (net (code "104") (name "unconnected-(U8-MISO-Pad9)") (class "Default")
      (node (ref "U8") (pin "9") (pinfunction "MISO_9") (pintype "unspecified+no_connect"))
    )
    (net (code "105") (name "unconnected-(U8-SD_CS-Pad15)") (class "Default")
      (node (ref "U8") (pin "15") (pinfunction "SD_CS_15") (pintype "unspecified+no_connect"))
    )
    (net (code "106") (name "unconnected-(U8-SD_MISO-Pad17)") (class "Default")
      (node (ref "U8") (pin "17") (pinfunction "SD_MISO_17") (pintype "unspecified+no_connect"))
    )
    (net (code "107") (name "unconnected-(U8-SD_MOSI-Pad16)") (class "Default")
      (node (ref "U8") (pin "16") (pinfunction "SD_MOSI_16") (pintype "unspecified+no_connect"))
    )
    (net (code "108") (name "unconnected-(U8-SD_SCK-Pad18)") (class "Default")
      (node (ref "U8") (pin "18") (pinfunction "SD_SCK_18") (pintype "unspecified+no_connect"))
    )
    (net (code "109") (name "unconnected-(U8-T_CLK-Pad10)") (class "Default")
      (node (ref "U8") (pin "10") (pinfunction "T_CLK_10") (pintype "unspecified+no_connect"))
    )
    (net (code "110") (name "unconnected-(U8-T_CS-Pad11)") (class "Default")
      (node (ref "U8") (pin "11") (pinfunction "T_CS_11") (pintype "unspecified+no_connect"))
    )
    (net (code "111") (name "unconnected-(U8-T_DIN-Pad12)") (class "Default")
      (node (ref "U8") (pin "12") (pinfunction "T_DIN_12") (pintype "unspecified+no_connect"))
    )
    (net (code "112") (name "unconnected-(U8-T_DO-Pad13)") (class "Default")
      (node (ref "U8") (pin "13") (pinfunction "T_DO_13") (pintype "unspecified+no_connect"))
    )
    (net (code "113") (name "unconnected-(U8-T_IRQ-Pad14)") (class "Default")
      (node (ref "U8") (pin "14") (pinfunction "T_IRQ_14") (pintype "unspecified+no_connect"))
    )
    (net (code "114") (name "unconnected-(U9-GP0-Pad12)") (class "Default")
      (node (ref "U9") (pin "12") (pinfunction "GP0_12") (pintype "unspecified+no_connect"))
    )
    (net (code "115") (name "unconnected-(U9-NC-Pad7)") (class "Default")
      (node (ref "U9") (pin "7") (pinfunction "NC_7") (pintype "unspecified+no_connect"))
    )
    (net (code "116") (name "unconnected-(U9-N{slash}C-Pad10)") (class "Default")
      (node (ref "U9") (pin "10") (pinfunction "N/C_10") (pintype "unspecified+no_connect"))
    )
    (net (code "117") (name "unconnected-(U9-N{slash}C-Pad11)") (class "Default")
      (node (ref "U9") (pin "11") (pinfunction "N/C_11") (pintype "unspecified+no_connect"))
    )
    (net (code "118") (name "unconnected-(U11-GP6-Pad18)") (class "Default")
      (node (ref "U11") (pin "18") (pinfunction "GP6_18") (pintype "unspecified+no_connect"))
    )
    (net (code "119") (name "unconnected-(U11-GP7-Pad19)") (class "Default")
      (node (ref "U11") (pin "19") (pinfunction "GP7_19") (pintype "unspecified+no_connect"))
    )
    (net (code "120") (name "unconnected-(U11-NC-Pad7)") (class "Default")
      (node (ref "U11") (pin "7") (pinfunction "NC_7") (pintype "unspecified+no_connect"))
    )
    (net (code "121") (name "unconnected-(U11-N{slash}C-Pad10)") (class "Default")
      (node (ref "U11") (pin "10") (pinfunction "N/C_10") (pintype "unspecified+no_connect"))
    )
    (net (code "122") (name "unconnected-(U11-N{slash}C-Pad11)") (class "Default")
      (node (ref "U11") (pin "11") (pinfunction "N/C_11") (pintype "unspecified+no_connect"))
    )
    (net (code "123") (name "unconnected-(U12-INT-Pad8)") (class "Default")
      (node (ref "U12") (pin "8") (pinfunction "INT_8") (pintype "unspecified+no_connect"))
    )
    (net (code "124") (name "unconnected-(U12-NC-Pad7)") (class "Default")
      (node (ref "U12") (pin "7") (pinfunction "NC_7") (pintype "unspecified+no_connect"))
    )
    (net (code "125") (name "unconnected-(U12-N{slash}C-Pad10)") (class "Default")
      (node (ref "U12") (pin "10") (pinfunction "N/C_10") (pintype "unspecified+no_connect"))
    )
    (net (code "126") (name "unconnected-(U12-N{slash}C-Pad11)") (class "Default")
      (node (ref "U12") (pin "11") (pinfunction "N/C_11") (pintype "unspecified+no_connect"))
    )
  )
)
